# Framework.net
KiCad netlist of a schematic drawn in EAGLE
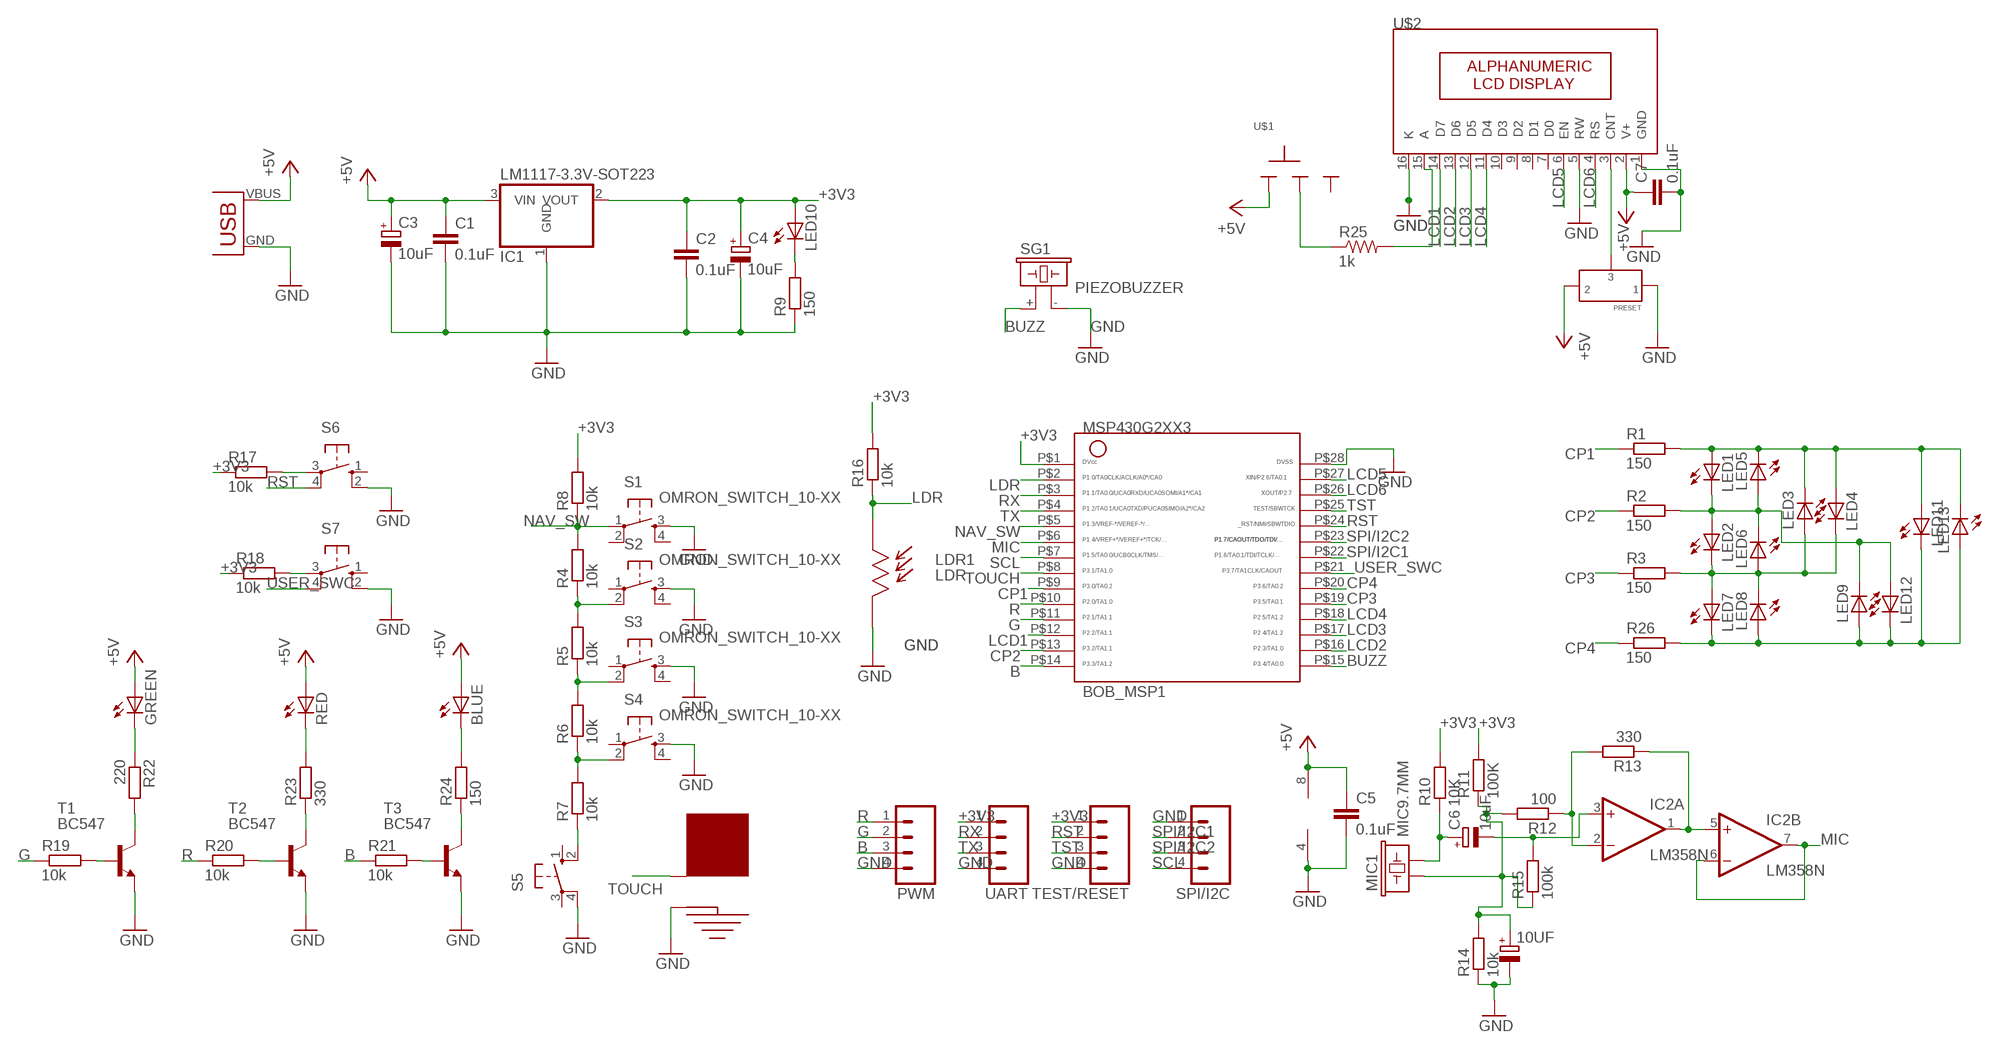
[diagram p0: schematic, sheet 1]

(export (version "E")
  (design (tool "Eeschema 10.0.6"))
  (components
    (comp (ref "10UF")
      (value "CAPACITOR-ELECTROLYTICE2.5-6")
      (footprint "eagle-import:E2,5-6")
      (libsource (lib "eagle-import") (part "CAPACITOR-ELECTROLYTICE2.5-6"))
    )
    (comp (ref "BLUE")
      (value "LED-BLU-5MM")
      (footprint "eagle-import:LED-5MM")
      (libsource (lib "eagle-import") (part "LED5MM-BLU-"))
    )
    (comp (ref "BOB_MSP1")
      (value "BOB_MSP_28PIN")
      (footprint "eagle-import:BOB_MSP_28PIN")
      (libsource (lib "eagle-import") (part "BOB_MSP_28PIN"))
    )
    (comp (ref "C1")
      (value "0.1uF")
      (footprint "eagle-import:C025-025X050")
      (libsource (lib "eagle-import") (part "CAPACITOR-CERAMIC025-025X050"))
    )
    (comp (ref "C2")
      (value "0.1uF")
      (footprint "eagle-import:C025-025X050")
      (libsource (lib "eagle-import") (part "CAPACITOR-CERAMIC025-025X050"))
    )
    (comp (ref "C3")
      (value "10uF")
      (footprint "eagle-import:E2,5-6")
      (libsource (lib "eagle-import") (part "CAPACITOR-ELECTROLYTICE2.5-6"))
    )
    (comp (ref "C4")
      (value "10uF")
      (footprint "eagle-import:E2,5-6")
      (libsource (lib "eagle-import") (part "CAPACITOR-ELECTROLYTICE2.5-6"))
    )
    (comp (ref "C5")
      (value "0.1uF")
      (footprint "eagle-import:C025-025X050")
      (libsource (lib "eagle-import") (part "CAPACITOR-CERAMIC025-025X050"))
    )
    (comp (ref "C6")
      (value "10uF")
      (footprint "eagle-import:E2,5-6")
      (libsource (lib "eagle-import") (part "CAPACITOR-ELECTROLYTICE2.5-6"))
    )
    (comp (ref "C7")
      (value "0.1uF")
      (footprint "eagle-import:C025-025X050")
      (libsource (lib "eagle-import") (part "CAPACITOR-CERAMIC025-025X050"))
    )
    (comp (ref "GREEN")
      (value "LED-RED-5MM")
      (footprint "eagle-import:LED-5MM")
      (libsource (lib "eagle-import") (part "LED5MM-RED-"))
    )
    (comp (ref "IC1")
      (value "LM1117-3.3V-SOT223")
      (footprint "eagle-import:SOT223")
      (libsource (lib "eagle-import") (part "LM1117-SOT223-3.3V"))
    )
    (comp (ref "IC2")
      (value "LM358N")
      (footprint "eagle-import:DIL08")
      (libsource (lib "eagle-import") (part "LM358N"))
    )
    (comp (ref "LDR1")
      (value "LDR")
      (footprint "eagle-import:LDR-5MM")
      (libsource (lib "eagle-import") (part "LDR"))
    )
    (comp (ref "LED1")
      (value "LED-RED-3MM")
      (footprint "eagle-import:LED-3MM")
      (libsource (lib "eagle-import") (part "LED3MM-RED-"))
    )
    (comp (ref "LED2")
      (value "LED-RED-3MM")
      (footprint "eagle-import:LED-3MM")
      (libsource (lib "eagle-import") (part "LED3MM-RED-"))
    )
    (comp (ref "LED3")
      (value "LED-RED-3MM")
      (footprint "eagle-import:LED-3MM")
      (libsource (lib "eagle-import") (part "LED3MM-RED-"))
    )
    (comp (ref "LED4")
      (value "LED-RED-3MM")
      (footprint "eagle-import:LED-3MM")
      (libsource (lib "eagle-import") (part "LED3MM-RED-"))
    )
    (comp (ref "LED5")
      (value "LED-RED-3MM")
      (footprint "eagle-import:LED-3MM")
      (libsource (lib "eagle-import") (part "LED3MM-RED-"))
    )
    (comp (ref "LED6")
      (value "LED-RED-3MM")
      (footprint "eagle-import:LED-3MM")
      (libsource (lib "eagle-import") (part "LED3MM-RED-"))
    )
    (comp (ref "LED7")
      (value "LED-RED-3MM")
      (footprint "eagle-import:LED-3MM")
      (libsource (lib "eagle-import") (part "LED3MM-RED-"))
    )
    (comp (ref "LED8")
      (value "LED-RED-3MM")
      (footprint "eagle-import:LED-3MM")
      (libsource (lib "eagle-import") (part "LED3MM-RED-"))
    )
    (comp (ref "LED9")
      (value "LED-RED-3MM")
      (footprint "eagle-import:LED-3MM")
      (libsource (lib "eagle-import") (part "LED3MM-RED-"))
    )
    (comp (ref "LED10")
      (value "LED-RED-3MM")
      (footprint "eagle-import:LED-3MM")
      (libsource (lib "eagle-import") (part "LED3MM-RED-"))
    )
    (comp (ref "LED11")
      (value "LED-RED-3MM")
      (footprint "eagle-import:LED-3MM")
      (libsource (lib "eagle-import") (part "LED3MM-RED-"))
    )
    (comp (ref "LED12")
      (value "LED-RED-3MM")
      (footprint "eagle-import:LED-3MM")
      (libsource (lib "eagle-import") (part "LED3MM-RED-"))
    )
    (comp (ref "LED13")
      (value "LED-RED-3MM")
      (footprint "eagle-import:LED-3MM")
      (libsource (lib "eagle-import") (part "LED3MM-RED-"))
    )
    (comp (ref "MIC1")
      (value "MIC9.7MM")
      (footprint "eagle-import:MIC-9.7MM")
      (libsource (lib "eagle-import") (part "MIC9.7MM"))
    )
    (comp (ref "PWM")
      (value "M04")
      (footprint "eagle-import:04P")
      (libsource (lib "eagle-import") (part "M04"))
    )
    (comp (ref "R1")
      (value "150")
      (footprint "eagle-import:0204_7")
      (libsource (lib "eagle-import") (part "RESISTOR-1/8W"))
    )
    (comp (ref "R2")
      (value "150")
      (footprint "eagle-import:0204_7")
      (libsource (lib "eagle-import") (part "RESISTOR-1/8W"))
    )
    (comp (ref "R3")
      (value "150")
      (footprint "eagle-import:0204_7")
      (libsource (lib "eagle-import") (part "RESISTOR-1/8W"))
    )
    (comp (ref "R4")
      (value "10k")
      (footprint "eagle-import:0204_7")
      (libsource (lib "eagle-import") (part "RESISTOR-1/8W"))
    )
    (comp (ref "R5")
      (value "10k")
      (footprint "eagle-import:0204_7")
      (libsource (lib "eagle-import") (part "RESISTOR-1/8W"))
    )
    (comp (ref "R6")
      (value "10k")
      (footprint "eagle-import:0204_7")
      (libsource (lib "eagle-import") (part "RESISTOR-1/8W"))
    )
    (comp (ref "R7")
      (value "10k")
      (footprint "eagle-import:0204_7")
      (libsource (lib "eagle-import") (part "RESISTOR-1/8W"))
    )
    (comp (ref "R8")
      (value "10k")
      (footprint "eagle-import:0204_7")
      (libsource (lib "eagle-import") (part "RESISTOR-1/8W"))
    )
    (comp (ref "R9")
      (value "150")
      (footprint "eagle-import:0204_7")
      (libsource (lib "eagle-import") (part "RESISTOR-1/8W"))
    )
    (comp (ref "R10")
      (value "10K")
      (footprint "eagle-import:0204_7")
      (libsource (lib "eagle-import") (part "RESISTOR-1/8W"))
    )
    (comp (ref "R11")
      (value "100K")
      (footprint "eagle-import:0204_7")
      (libsource (lib "eagle-import") (part "RESISTOR-1/8W"))
    )
    (comp (ref "R12")
      (value "100")
      (footprint "eagle-import:0204_7")
      (libsource (lib "eagle-import") (part "RESISTOR-1/8W"))
    )
    (comp (ref "R13")
      (value "330")
      (footprint "eagle-import:0204_7")
      (libsource (lib "eagle-import") (part "RESISTOR-1/8W"))
    )
    (comp (ref "R14")
      (value "10k")
      (footprint "eagle-import:0204_7")
      (libsource (lib "eagle-import") (part "RESISTOR-1/8W"))
    )
    (comp (ref "R15")
      (value "100k")
      (footprint "eagle-import:0204_7")
      (libsource (lib "eagle-import") (part "RESISTOR-1/8W"))
    )
    (comp (ref "R16")
      (value "10k")
      (footprint "eagle-import:0204_7")
      (libsource (lib "eagle-import") (part "RESISTOR-1/8W"))
    )
    (comp (ref "R17")
      (value "10k")
      (footprint "eagle-import:0204_7")
      (libsource (lib "eagle-import") (part "RESISTOR-1/8W"))
    )
    (comp (ref "R18")
      (value "10k")
      (footprint "eagle-import:0204_7")
      (libsource (lib "eagle-import") (part "RESISTOR-1/8W"))
    )
    (comp (ref "R19")
      (value "10k")
      (footprint "eagle-import:0204_7")
      (libsource (lib "eagle-import") (part "RESISTOR-1/8W"))
    )
    (comp (ref "R20")
      (value "10k")
      (footprint "eagle-import:0204_7")
      (libsource (lib "eagle-import") (part "RESISTOR-1/8W"))
    )
    (comp (ref "R21")
      (value "10k")
      (footprint "eagle-import:0204_7")
      (libsource (lib "eagle-import") (part "RESISTOR-1/8W"))
    )
    (comp (ref "R22")
      (value "220")
      (footprint "eagle-import:0204_7")
      (libsource (lib "eagle-import") (part "RESISTOR-1/8W"))
    )
    (comp (ref "R23")
      (value "330")
      (footprint "eagle-import:0204_7")
      (libsource (lib "eagle-import") (part "RESISTOR-1/8W"))
    )
    (comp (ref "R24")
      (value "150")
      (footprint "eagle-import:0204_7")
      (libsource (lib "eagle-import") (part "RESISTOR-1/8W"))
    )
    (comp (ref "R25")
      (value "1k")
      (footprint "eagle-import:0207_10")
      (libsource (lib "eagle-import") (part "RESISTOR0207/10"))
    )
    (comp (ref "R26")
      (value "150")
      (footprint "eagle-import:0204_7")
      (libsource (lib "eagle-import") (part "RESISTOR-1/8W"))
    )
    (comp (ref "RED")
      (value "LED-GRN-5MM")
      (footprint "eagle-import:LED-5MM")
      (libsource (lib "eagle-import") (part "LED5MM-GRN-"))
    )
    (comp (ref "S1")
      (value "OMRON_SWITCH_10-XX")
      (footprint "eagle-import:B3F-10XX")
      (libsource (lib "eagle-import") (part "OMRON_SWITCH_10-XX"))
    )
    (comp (ref "S2")
      (value "OMRON_SWITCH_10-XX")
      (footprint "eagle-import:B3F-10XX")
      (libsource (lib "eagle-import") (part "OMRON_SWITCH_10-XX"))
    )
    (comp (ref "S3")
      (value "OMRON_SWITCH_10-XX")
      (footprint "eagle-import:B3F-10XX")
      (libsource (lib "eagle-import") (part "OMRON_SWITCH_10-XX"))
    )
    (comp (ref "S4")
      (value "OMRON_SWITCH_10-XX")
      (footprint "eagle-import:B3F-10XX")
      (libsource (lib "eagle-import") (part "OMRON_SWITCH_10-XX"))
    )
    (comp (ref "S5")
      (value "PUSH-BUTTON-6MM")
      (footprint "eagle-import:B3F-10XX")
      (libsource (lib "eagle-import") (part "PUSH-BUTTON-6MM"))
    )
    (comp (ref "S6")
      (value "10-XX")
      (footprint "eagle-import:B3F-10XX")
      (fields (field (name "MPN") "B3F-1000"))
      (libsource (lib "eagle-import") (part "10-XX"))
    )
    (comp (ref "S7")
      (value "10-XX")
      (footprint "eagle-import:B3F-10XX")
      (fields (field (name "MPN") "B3F-1000"))
      (libsource (lib "eagle-import") (part "10-XX"))
    )
    (comp (ref "SG1")
      (value "PIEZOBUZZER")
      (footprint "eagle-import:PIEZOBUZZER")
      (libsource (lib "eagle-import") (part "PIEZOBUZZER"))
    )
    (comp (ref "SPI/I2C")
      (value "M04")
      (footprint "eagle-import:04P")
      (libsource (lib "eagle-import") (part "M04"))
    )
    (comp (ref "T1")
      (value "BC547")
      (footprint "eagle-import:TO92")
      (libsource (lib "eagle-import") (part "BC547"))
    )
    (comp (ref "T2")
      (value "BC547")
      (footprint "eagle-import:TO92")
      (libsource (lib "eagle-import") (part "BC547"))
    )
    (comp (ref "T3")
      (value "BC547")
      (footprint "eagle-import:TO92")
      (libsource (lib "eagle-import") (part "BC547"))
    )
    (comp (ref "TEST/RESET")
      (value "M04")
      (footprint "eagle-import:04P")
      (libsource (lib "eagle-import") (part "M04"))
    )
    (comp (ref "TOUCH1")
      (value "TOUCHPAD-20MM")
      (footprint "eagle-import:TOUCHPAD-20MM")
      (libsource (lib "eagle-import") (part "TOUCHPAD-20MM"))
    )
    (comp (ref "U$1")
      (value "SLIDE-SWITCH-BIG")
      (footprint "eagle-import:SLIDE-SPDT-2.5X5-WITH-SUPPORT")
      (libsource (lib "eagle-import") (part "SLIDE-SWITCH-BIG"))
    )
    (comp (ref "U$2")
      (value "CHAR-LCD-16X2")
      (footprint "eagle-import:16X2-LCD-WITH-MOUNT")
      (libsource (lib "eagle-import") (part "CHAR-LCD-16X2"))
    )
    (comp (ref "U$3")
      (value "USB-POWER")
      (footprint "eagle-import:MINI-USB-POWER")
      (libsource (lib "eagle-import") (part "USB-POWER"))
    )
    (comp (ref "U$4")
      (value "PRESET")
      (footprint "eagle-import:PRESET-LR")
      (libsource (lib "eagle-import") (part "PRESET"))
    )
    (comp (ref "UART")
      (value "M04")
      (footprint "eagle-import:04P")
      (libsource (lib "eagle-import") (part "M04"))
    )
  )
  (nets
    (net (code "1") (name "+5V") (class "Default")
      (node (ref "BLUE") (pin "A") (pinfunction "A_A") (pintype "passive"))
      (node (ref "C1") (pin "1") (pinfunction "1_1") (pintype "passive"))
      (node (ref "C3") (pin "+") (pinfunction "+_+") (pintype "passive"))
      (node (ref "C5") (pin "1") (pinfunction "1_1") (pintype "passive"))
      (node (ref "C7") (pin "1") (pinfunction "1_1") (pintype "passive"))
      (node (ref "GREEN") (pin "A") (pinfunction "A_A") (pintype "passive"))
      (node (ref "IC1") (pin "3") (pinfunction "VIN_3") (pintype "input"))
      (node (ref "IC2") (pin "8") (pinfunction "V+_8") (pintype "power_in"))
      (node (ref "RED") (pin "A") (pinfunction "A_A") (pintype "passive"))
      (node (ref "U$1") (pin "1") (pinfunction "1_1") (pintype "bidirectional"))
      (node (ref "U$2") (pin "2") (pinfunction "V+_2") (pintype "power_in"))
      (node (ref "U$3") (pin "VBUS") (pinfunction "VCC_VBUS") (pintype "power_in"))
      (node (ref "U$4") (pin "P$2") (pinfunction "2_P$2") (pintype "passive"))
    )
    (net (code "2") (name "/+3V3") (class "Default")
      (node (ref "BOB_MSP1") (pin "P$1") (pinfunction "1_P$1") (pintype "bidirectional"))
      (node (ref "C2") (pin "1") (pinfunction "1_1") (pintype "passive"))
      (node (ref "C4") (pin "+") (pinfunction "+_+") (pintype "passive"))
      (node (ref "IC1") (pin "2") (pinfunction "VOUT_2") (pintype "output"))
      (node (ref "LED10") (pin "A") (pinfunction "A_A") (pintype "passive"))
      (node (ref "R10") (pin "2") (pinfunction "2_2") (pintype "passive"))
      (node (ref "R11") (pin "2") (pinfunction "2_2") (pintype "passive"))
      (node (ref "R16") (pin "2") (pinfunction "2_2") (pintype "passive"))
      (node (ref "R17") (pin "1") (pinfunction "1_1") (pintype "passive"))
      (node (ref "R18") (pin "1") (pinfunction "1_1") (pintype "passive"))
      (node (ref "R8") (pin "2") (pinfunction "2_2") (pintype "passive"))
      (node (ref "TEST/RESET") (pin "1") (pinfunction "1_1") (pintype "passive"))
      (node (ref "UART") (pin "1") (pinfunction "1_1") (pintype "passive"))
    )
    (net (code "3") (name "/B") (class "Default")
      (node (ref "BOB_MSP1") (pin "P$14") (pinfunction "14_P$14") (pintype "bidirectional"))
      (node (ref "PWM") (pin "3") (pinfunction "3_3") (pintype "passive"))
      (node (ref "R21") (pin "1") (pinfunction "1_1") (pintype "passive"))
    )
    (net (code "4") (name "/BUZZ") (class "Default")
      (node (ref "BOB_MSP1") (pin "P$15") (pinfunction "15_P$15") (pintype "bidirectional"))
      (node (ref "SG1") (pin "+") (pinfunction "1_+") (pintype "passive"))
    )
    (net (code "5") (name "/CP1") (class "Default")
      (node (ref "BOB_MSP1") (pin "P$9") (pinfunction "9_P$9") (pintype "bidirectional"))
      (node (ref "R1") (pin "1") (pinfunction "1_1") (pintype "passive"))
    )
    (net (code "6") (name "/CP2") (class "Default")
      (node (ref "BOB_MSP1") (pin "P$13") (pinfunction "13_P$13") (pintype "bidirectional"))
      (node (ref "R2") (pin "1") (pinfunction "1_1") (pintype "passive"))
    )
    (net (code "7") (name "/CP3") (class "Default")
      (node (ref "BOB_MSP1") (pin "P$19") (pinfunction "19_P$19") (pintype "bidirectional"))
      (node (ref "R3") (pin "1") (pinfunction "1_1") (pintype "passive"))
    )
    (net (code "8") (name "/CP4") (class "Default")
      (node (ref "BOB_MSP1") (pin "P$20") (pinfunction "20_P$20") (pintype "bidirectional"))
      (node (ref "R26") (pin "1") (pinfunction "1_1") (pintype "passive"))
    )
    (net (code "9") (name "/G") (class "Default")
      (node (ref "BOB_MSP1") (pin "P$11") (pinfunction "11_P$11") (pintype "bidirectional"))
      (node (ref "PWM") (pin "2") (pinfunction "2_2") (pintype "passive"))
      (node (ref "R19") (pin "1") (pinfunction "1_1") (pintype "passive"))
    )
    (net (code "10") (name "/LCD1") (class "Default")
      (node (ref "BOB_MSP1") (pin "P$12") (pinfunction "12_P$12") (pintype "bidirectional"))
      (node (ref "U$2") (pin "14") (pinfunction "D7_14") (pintype "bidirectional"))
    )
    (net (code "11") (name "/LCD2") (class "Default")
      (node (ref "BOB_MSP1") (pin "P$16") (pinfunction "16_P$16") (pintype "bidirectional"))
      (node (ref "U$2") (pin "13") (pinfunction "D6_13") (pintype "bidirectional"))
    )
    (net (code "12") (name "/LCD3") (class "Default")
      (node (ref "BOB_MSP1") (pin "P$17") (pinfunction "17_P$17") (pintype "bidirectional"))
      (node (ref "U$2") (pin "12") (pinfunction "D5_12") (pintype "bidirectional"))
    )
    (net (code "13") (name "/LCD4") (class "Default")
      (node (ref "BOB_MSP1") (pin "P$18") (pinfunction "18_P$18") (pintype "bidirectional"))
      (node (ref "U$2") (pin "11") (pinfunction "D4_11") (pintype "bidirectional"))
    )
    (net (code "14") (name "/LCD5") (class "Default")
      (node (ref "BOB_MSP1") (pin "P$27") (pinfunction "27_P$27") (pintype "bidirectional"))
      (node (ref "U$2") (pin "6") (pinfunction "EN_6") (pintype "bidirectional"))
    )
    (net (code "15") (name "/LCD6") (class "Default")
      (node (ref "BOB_MSP1") (pin "P$26") (pinfunction "26_P$26") (pintype "bidirectional"))
      (node (ref "U$2") (pin "4") (pinfunction "RS_4") (pintype "bidirectional"))
    )
    (net (code "16") (name "/LDR") (class "Default")
      (node (ref "BOB_MSP1") (pin "P$2") (pinfunction "2_P$2") (pintype "bidirectional"))
      (node (ref "LDR1") (pin "P$1") (pinfunction "P$1_P$1") (pintype "bidirectional"))
      (node (ref "R16") (pin "1") (pinfunction "1_1") (pintype "passive"))
    )
    (net (code "17") (name "/MIC") (class "Default")
      (node (ref "BOB_MSP1") (pin "P$6") (pinfunction "6_P$6") (pintype "bidirectional"))
      (node (ref "IC2") (pin "6") (pinfunction "-IN_6") (pintype "input"))
      (node (ref "IC2") (pin "7") (pinfunction "OUT_7") (pintype "output"))
    )
    (net (code "18") (name "/NAV_SW") (class "Default")
      (node (ref "BOB_MSP1") (pin "P$5") (pinfunction "5_P$5") (pintype "bidirectional"))
      (node (ref "R4") (pin "2") (pinfunction "2_2") (pintype "passive"))
      (node (ref "R8") (pin "1") (pinfunction "1_1") (pintype "passive"))
      (node (ref "S1") (pin "1") (pinfunction "P_1") (pintype "passive"))
    )
    (net (code "19") (name "/R") (class "Default")
      (node (ref "BOB_MSP1") (pin "P$10") (pinfunction "10_P$10") (pintype "bidirectional"))
      (node (ref "PWM") (pin "1") (pinfunction "1_1") (pintype "passive"))
      (node (ref "R20") (pin "1") (pinfunction "1_1") (pintype "passive"))
    )
    (net (code "20") (name "/RST") (class "Default")
      (node (ref "BOB_MSP1") (pin "P$24") (pinfunction "24_P$24") (pintype "bidirectional"))
      (node (ref "S6") (pin "4") (pinfunction "P1_4") (pintype "passive"))
      (node (ref "TEST/RESET") (pin "2") (pinfunction "2_2") (pintype "passive"))
    )
    (net (code "21") (name "/RX") (class "Default")
      (node (ref "BOB_MSP1") (pin "P$3") (pinfunction "3_P$3") (pintype "bidirectional"))
      (node (ref "UART") (pin "2") (pinfunction "2_2") (pintype "passive"))
    )
    (net (code "22") (name "/SCL") (class "Default")
      (node (ref "BOB_MSP1") (pin "P$7") (pinfunction "7_P$7") (pintype "bidirectional"))
      (node (ref "SPI/I2C") (pin "4") (pinfunction "4_4") (pintype "passive"))
    )
    (net (code "23") (name "/SPI{slash}I2C1") (class "Default")
      (node (ref "BOB_MSP1") (pin "P$22") (pinfunction "22_P$22") (pintype "bidirectional"))
      (node (ref "SPI/I2C") (pin "2") (pinfunction "2_2") (pintype "passive"))
    )
    (net (code "24") (name "/SPI{slash}I2C2") (class "Default")
      (node (ref "BOB_MSP1") (pin "P$23") (pinfunction "23_P$23") (pintype "bidirectional"))
      (node (ref "SPI/I2C") (pin "3") (pinfunction "3_3") (pintype "passive"))
    )
    (net (code "25") (name "/TOUCH") (class "Default")
      (node (ref "BOB_MSP1") (pin "P$8") (pinfunction "8_P$8") (pintype "bidirectional"))
      (node (ref "TOUCH1") (pin "TOUCH") (pinfunction "TOUCH_TOUCH") (pintype "passive"))
    )
    (net (code "26") (name "/TST") (class "Default")
      (node (ref "BOB_MSP1") (pin "P$25") (pinfunction "25_P$25") (pintype "bidirectional"))
      (node (ref "TEST/RESET") (pin "3") (pinfunction "3_3") (pintype "passive"))
    )
    (net (code "27") (name "/TX") (class "Default")
      (node (ref "BOB_MSP1") (pin "P$4") (pinfunction "4_P$4") (pintype "bidirectional"))
      (node (ref "UART") (pin "3") (pinfunction "3_3") (pintype "passive"))
    )
    (net (code "28") (name "/USER_SWC") (class "Default")
      (node (ref "BOB_MSP1") (pin "P$21") (pinfunction "21_P$21") (pintype "bidirectional"))
      (node (ref "S7") (pin "4") (pinfunction "P1_4") (pintype "passive"))
    )
    (net (code "29") (name "GND") (class "Default")
      (node (ref "10UF") (pin "-") (pinfunction "-_-") (pintype "passive"))
      (node (ref "BOB_MSP1") (pin "P$28") (pinfunction "28_P$28") (pintype "bidirectional"))
      (node (ref "C1") (pin "2") (pinfunction "2_2") (pintype "passive"))
      (node (ref "C2") (pin "2") (pinfunction "2_2") (pintype "passive"))
      (node (ref "C3") (pin "-") (pinfunction "-_-") (pintype "passive"))
      (node (ref "C4") (pin "-") (pinfunction "-_-") (pintype "passive"))
      (node (ref "C5") (pin "2") (pinfunction "2_2") (pintype "passive"))
      (node (ref "C7") (pin "2") (pinfunction "2_2") (pintype "passive"))
      (node (ref "IC1") (pin "1") (pinfunction "GND_1") (pintype "power_in"))
      (node (ref "IC2") (pin "4") (pinfunction "V-_4") (pintype "power_in"))
      (node (ref "LDR1") (pin "P$2") (pinfunction "P$2_P$2") (pintype "bidirectional"))
      (node (ref "PWM") (pin "4") (pinfunction "4_4") (pintype "passive"))
      (node (ref "R14") (pin "1") (pinfunction "1_1") (pintype "passive"))
      (node (ref "R9") (pin "1") (pinfunction "1_1") (pintype "passive"))
      (node (ref "S1") (pin "3") (pinfunction "S_3") (pintype "passive"))
      (node (ref "S2") (pin "3") (pinfunction "S_3") (pintype "passive"))
      (node (ref "S3") (pin "3") (pinfunction "S_3") (pintype "passive"))
      (node (ref "S4") (pin "3") (pinfunction "S_3") (pintype "passive"))
      (node (ref "S5") (pin "4") (pinfunction "P1_4") (pintype "passive"))
      (node (ref "S6") (pin "2") (pinfunction "S1_2") (pintype "passive"))
      (node (ref "S7") (pin "2") (pinfunction "S1_2") (pintype "passive"))
      (node (ref "SG1") (pin "-") (pinfunction "2_-") (pintype "passive"))
      (node (ref "SPI/I2C") (pin "1") (pinfunction "1_1") (pintype "passive"))
      (node (ref "T1") (pin "1") (pinfunction "E_1") (pintype "passive"))
      (node (ref "T2") (pin "1") (pinfunction "E_1") (pintype "passive"))
      (node (ref "T3") (pin "1") (pinfunction "E_1") (pintype "passive"))
      (node (ref "TEST/RESET") (pin "4") (pinfunction "4_4") (pintype "passive"))
      (node (ref "TOUCH1") (pin "GND") (pinfunction "GND_GND") (pintype "passive"))
      (node (ref "U$2") (pin "1") (pinfunction "GND_1") (pintype "power_in"))
      (node (ref "U$2") (pin "16") (pinfunction "K_16") (pintype "bidirectional"))
      (node (ref "U$2") (pin "5") (pinfunction "RW_5") (pintype "bidirectional"))
      (node (ref "U$3") (pin "GND") (pinfunction "GND_GND") (pintype "power_in"))
      (node (ref "U$4") (pin "P$1") (pinfunction "1_P$1") (pintype "passive"))
      (node (ref "UART") (pin "4") (pinfunction "4_4") (pintype "passive"))
    )
    (net (code "30") (name "Net-(10UF-Pad+)") (class "Default")
      (node (ref "10UF") (pin "+") (pinfunction "+_+") (pintype "passive"))
      (node (ref "MIC1") (pin "1") (pinfunction "1_1") (pintype "passive"))
      (node (ref "R11") (pin "1") (pinfunction "1_1") (pintype "passive"))
      (node (ref "R12") (pin "2") (pinfunction "2_2") (pintype "passive"))
      (node (ref "R14") (pin "2") (pinfunction "2_2") (pintype "passive"))
      (node (ref "R15") (pin "1") (pinfunction "1_1") (pintype "passive"))
    )
    (net (code "31") (name "Net-(BLUE-C)") (class "Default")
      (node (ref "BLUE") (pin "K") (pinfunction "C_K") (pintype "passive"))
      (node (ref "R24") (pin "2") (pinfunction "2_2") (pintype "passive"))
    )
    (net (code "32") (name "Net-(C6-Pad+)") (class "Default")
      (node (ref "C6") (pin "+") (pinfunction "+_+") (pintype "passive"))
      (node (ref "MIC1") (pin "2") (pinfunction "2_2") (pintype "passive"))
      (node (ref "R10") (pin "1") (pinfunction "1_1") (pintype "passive"))
    )
    (net (code "33") (name "Net-(GREEN-C)") (class "Default")
      (node (ref "GREEN") (pin "K") (pinfunction "C_K") (pintype "passive"))
      (node (ref "R22") (pin "1") (pinfunction "1_1") (pintype "passive"))
    )
    (net (code "34") (name "Net-(IC2A-+IN)") (class "Default")
      (node (ref "C6") (pin "-") (pinfunction "-_-") (pintype "passive"))
      (node (ref "IC2") (pin "3") (pinfunction "+IN_3") (pintype "input"))
      (node (ref "R15") (pin "2") (pinfunction "2_2") (pintype "passive"))
    )
    (net (code "35") (name "Net-(IC2A--IN)") (class "Default")
      (node (ref "IC2") (pin "2") (pinfunction "-IN_2") (pintype "input"))
      (node (ref "R12") (pin "1") (pinfunction "1_1") (pintype "passive"))
      (node (ref "R13") (pin "2") (pinfunction "2_2") (pintype "passive"))
    )
    (net (code "36") (name "Net-(IC2A-OUT)") (class "Default")
      (node (ref "IC2") (pin "1") (pinfunction "OUT_1") (pintype "output"))
      (node (ref "IC2") (pin "5") (pinfunction "+IN_5") (pintype "input"))
      (node (ref "R13") (pin "1") (pinfunction "1_1") (pintype "passive"))
    )
    (net (code "37") (name "Net-(LED1-C)") (class "Default")
      (node (ref "LED1") (pin "K") (pinfunction "C_K") (pintype "passive"))
      (node (ref "LED12") (pin "A") (pinfunction "A_A") (pintype "passive"))
      (node (ref "LED2") (pin "A") (pinfunction "A_A") (pintype "passive"))
      (node (ref "LED5") (pin "A") (pinfunction "A_A") (pintype "passive"))
      (node (ref "LED6") (pin "K") (pinfunction "C_K") (pintype "passive"))
      (node (ref "LED9") (pin "K") (pinfunction "C_K") (pintype "passive"))
      (node (ref "R2") (pin "2") (pinfunction "2_2") (pintype "passive"))
    )
    (net (code "38") (name "Net-(LED2-C)") (class "Default")
      (node (ref "LED2") (pin "K") (pinfunction "C_K") (pintype "passive"))
      (node (ref "LED3") (pin "A") (pinfunction "A_A") (pintype "passive"))
      (node (ref "LED4") (pin "K") (pinfunction "C_K") (pintype "passive"))
      (node (ref "LED6") (pin "A") (pinfunction "A_A") (pintype "passive"))
      (node (ref "LED7") (pin "A") (pinfunction "A_A") (pintype "passive"))
      (node (ref "LED8") (pin "K") (pinfunction "C_K") (pintype "passive"))
      (node (ref "R3") (pin "2") (pinfunction "2_2") (pintype "passive"))
    )
    (net (code "39") (name "Net-(LED10-C)") (class "Default")
      (node (ref "LED10") (pin "K") (pinfunction "C_K") (pintype "passive"))
      (node (ref "R9") (pin "2") (pinfunction "2_2") (pintype "passive"))
    )
    (net (code "40") (name "Net-(LED11-C)") (class "Default")
      (node (ref "LED11") (pin "K") (pinfunction "C_K") (pintype "passive"))
      (node (ref "LED12") (pin "K") (pinfunction "C_K") (pintype "passive"))
      (node (ref "LED13") (pin "A") (pinfunction "A_A") (pintype "passive"))
      (node (ref "LED7") (pin "K") (pinfunction "C_K") (pintype "passive"))
      (node (ref "LED8") (pin "A") (pinfunction "A_A") (pintype "passive"))
      (node (ref "LED9") (pin "A") (pinfunction "A_A") (pintype "passive"))
      (node (ref "R26") (pin "2") (pinfunction "2_2") (pintype "passive"))
    )
    (net (code "41") (name "Net-(LED13-C)") (class "Default")
      (node (ref "LED1") (pin "A") (pinfunction "A_A") (pintype "passive"))
      (node (ref "LED11") (pin "A") (pinfunction "A_A") (pintype "passive"))
      (node (ref "LED13") (pin "K") (pinfunction "C_K") (pintype "passive"))
      (node (ref "LED3") (pin "K") (pinfunction "C_K") (pintype "passive"))
      (node (ref "LED4") (pin "A") (pinfunction "A_A") (pintype "passive"))
      (node (ref "LED5") (pin "K") (pinfunction "C_K") (pintype "passive"))
      (node (ref "R1") (pin "2") (pinfunction "2_2") (pintype "passive"))
    )
    (net (code "42") (name "Net-(R25-Pad1)") (class "Default")
      (node (ref "R25") (pin "1") (pinfunction "1_1") (pintype "passive"))
      (node (ref "U$1") (pin "2") (pinfunction "2_2") (pintype "bidirectional"))
    )
    (net (code "43") (name "Net-(RED-C)") (class "Default")
      (node (ref "R23") (pin "2") (pinfunction "2_2") (pintype "passive"))
      (node (ref "RED") (pin "K") (pinfunction "C_K") (pintype "passive"))
    )
    (net (code "44") (name "Net-(S2-P1)") (class "Default")
      (node (ref "R4") (pin "1") (pinfunction "1_1") (pintype "passive"))
      (node (ref "R5") (pin "2") (pinfunction "2_2") (pintype "passive"))
      (node (ref "S2") (pin "2") (pinfunction "P1_2") (pintype "passive"))
    )
    (net (code "45") (name "Net-(S3-P1)") (class "Default")
      (node (ref "R5") (pin "1") (pinfunction "1_1") (pintype "passive"))
      (node (ref "R6") (pin "2") (pinfunction "2_2") (pintype "passive"))
      (node (ref "S3") (pin "2") (pinfunction "P1_2") (pintype "passive"))
    )
    (net (code "46") (name "Net-(S4-P1)") (class "Default")
      (node (ref "R6") (pin "1") (pinfunction "1_1") (pintype "passive"))
      (node (ref "R7") (pin "2") (pinfunction "2_2") (pintype "passive"))
      (node (ref "S4") (pin "2") (pinfunction "P1_2") (pintype "passive"))
    )
    (net (code "47") (name "Net-(S5-S1)") (class "Default")
      (node (ref "R7") (pin "1") (pinfunction "1_1") (pintype "passive"))
      (node (ref "S5") (pin "2") (pinfunction "S1_2") (pintype "passive"))
    )
    (net (code "48") (name "Net-(S6-P)") (class "Default")
      (node (ref "R17") (pin "2") (pinfunction "2_2") (pintype "passive"))
      (node (ref "S6") (pin "3") (pinfunction "P_3") (pintype "passive"))
    )
    (net (code "49") (name "Net-(S7-P)") (class "Default")
      (node (ref "R18") (pin "2") (pinfunction "2_2") (pintype "passive"))
      (node (ref "S7") (pin "3") (pinfunction "P_3") (pintype "passive"))
    )
    (net (code "50") (name "Net-(T1-B)") (class "Default")
      (node (ref "R19") (pin "2") (pinfunction "2_2") (pintype "passive"))
      (node (ref "T1") (pin "2") (pinfunction "B_2") (pintype "passive"))
    )
    (net (code "51") (name "Net-(T1-C)") (class "Default")
      (node (ref "R22") (pin "2") (pinfunction "2_2") (pintype "passive"))
      (node (ref "T1") (pin "3") (pinfunction "C_3") (pintype "passive"))
    )
    (net (code "52") (name "Net-(T2-B)") (class "Default")
      (node (ref "R20") (pin "2") (pinfunction "2_2") (pintype "passive"))
      (node (ref "T2") (pin "2") (pinfunction "B_2") (pintype "passive"))
    )
    (net (code "53") (name "Net-(T2-C)") (class "Default")
      (node (ref "R23") (pin "1") (pinfunction "1_1") (pintype "passive"))
      (node (ref "T2") (pin "3") (pinfunction "C_3") (pintype "passive"))
    )
    (net (code "54") (name "Net-(T3-B)") (class "Default")
      (node (ref "R21") (pin "2") (pinfunction "2_2") (pintype "passive"))
      (node (ref "T3") (pin "2") (pinfunction "B_2") (pintype "passive"))
    )
    (net (code "55") (name "Net-(T3-C)") (class "Default")
      (node (ref "R24") (pin "1") (pinfunction "1_1") (pintype "passive"))
      (node (ref "T3") (pin "3") (pinfunction "C_3") (pintype "passive"))
    )
    (net (code "56") (name "Net-(U$2-A)") (class "Default")
      (node (ref "R25") (pin "2") (pinfunction "2_2") (pintype "passive"))
      (node (ref "U$2") (pin "15") (pinfunction "A_15") (pintype "bidirectional"))
    )
    (net (code "57") (name "Net-(U$2-CNT)") (class "Default")
      (node (ref "U$2") (pin "3") (pinfunction "CNT_3") (pintype "bidirectional"))
      (node (ref "U$4") (pin "P$3") (pinfunction "3_P$3") (pintype "passive"))
    )
    (net (code "58") (name "unconnected-(S1-P1-Pad2)") (class "Default")
      (node (ref "S1") (pin "2") (pinfunction "P1_2") (pintype "passive"))
    )
    (net (code "59") (name "unconnected-(S1-S1-Pad4)") (class "Default")
      (node (ref "S1") (pin "4") (pinfunction "S1_4") (pintype "passive"))
    )
    (net (code "60") (name "unconnected-(S2-P-Pad1)") (class "Default")
      (node (ref "S2") (pin "1") (pinfunction "P_1") (pintype "passive"))
    )
    (net (code "61") (name "unconnected-(S2-S1-Pad4)") (class "Default")
      (node (ref "S2") (pin "4") (pinfunction "S1_4") (pintype "passive"))
    )
    (net (code "62") (name "unconnected-(S3-P-Pad1)") (class "Default")
      (node (ref "S3") (pin "1") (pinfunction "P_1") (pintype "passive"))
    )
    (net (code "63") (name "unconnected-(S3-S1-Pad4)") (class "Default")
      (node (ref "S3") (pin "4") (pinfunction "S1_4") (pintype "passive"))
    )
    (net (code "64") (name "unconnected-(S4-P-Pad1)") (class "Default")
      (node (ref "S4") (pin "1") (pinfunction "P_1") (pintype "passive"))
    )
    (net (code "65") (name "unconnected-(S4-S1-Pad4)") (class "Default")
      (node (ref "S4") (pin "4") (pinfunction "S1_4") (pintype "passive"))
    )
    (net (code "66") (name "unconnected-(S5-P-Pad3)") (class "Default")
      (node (ref "S5") (pin "3") (pinfunction "P_3") (pintype "passive"))
    )
    (net (code "67") (name "unconnected-(S5-S-Pad1)") (class "Default")
      (node (ref "S5") (pin "1") (pinfunction "S_1") (pintype "passive"))
    )
    (net (code "68") (name "unconnected-(S6-S-Pad1)") (class "Default")
      (node (ref "S6") (pin "1") (pinfunction "S_1") (pintype "passive"))
    )
    (net (code "69") (name "unconnected-(S7-S-Pad1)") (class "Default")
      (node (ref "S7") (pin "1") (pinfunction "S_1") (pintype "passive"))
    )
    (net (code "70") (name "unconnected-(U$1-Pad3)") (class "Default")
      (node (ref "U$1") (pin "3") (pinfunction "3_3") (pintype "bidirectional"))
    )
    (net (code "71") (name "unconnected-(U$2-D0-Pad7)") (class "Default")
      (node (ref "U$2") (pin "7") (pinfunction "D0_7") (pintype "bidirectional"))
    )
    (net (code "72") (name "unconnected-(U$2-D1-Pad8)") (class "Default")
      (node (ref "U$2") (pin "8") (pinfunction "D1_8") (pintype "bidirectional"))
    )
    (net (code "73") (name "unconnected-(U$2-D2-Pad9)") (class "Default")
      (node (ref "U$2") (pin "9") (pinfunction "D2_9") (pintype "bidirectional"))
    )
    (net (code "74") (name "unconnected-(U$2-D3-Pad10)") (class "Default")
      (node (ref "U$2") (pin "10") (pinfunction "D3_10") (pintype "bidirectional"))
    )
  )
)
